# Main.net
KiCad netlist of a schematic drawn in Altium Designer
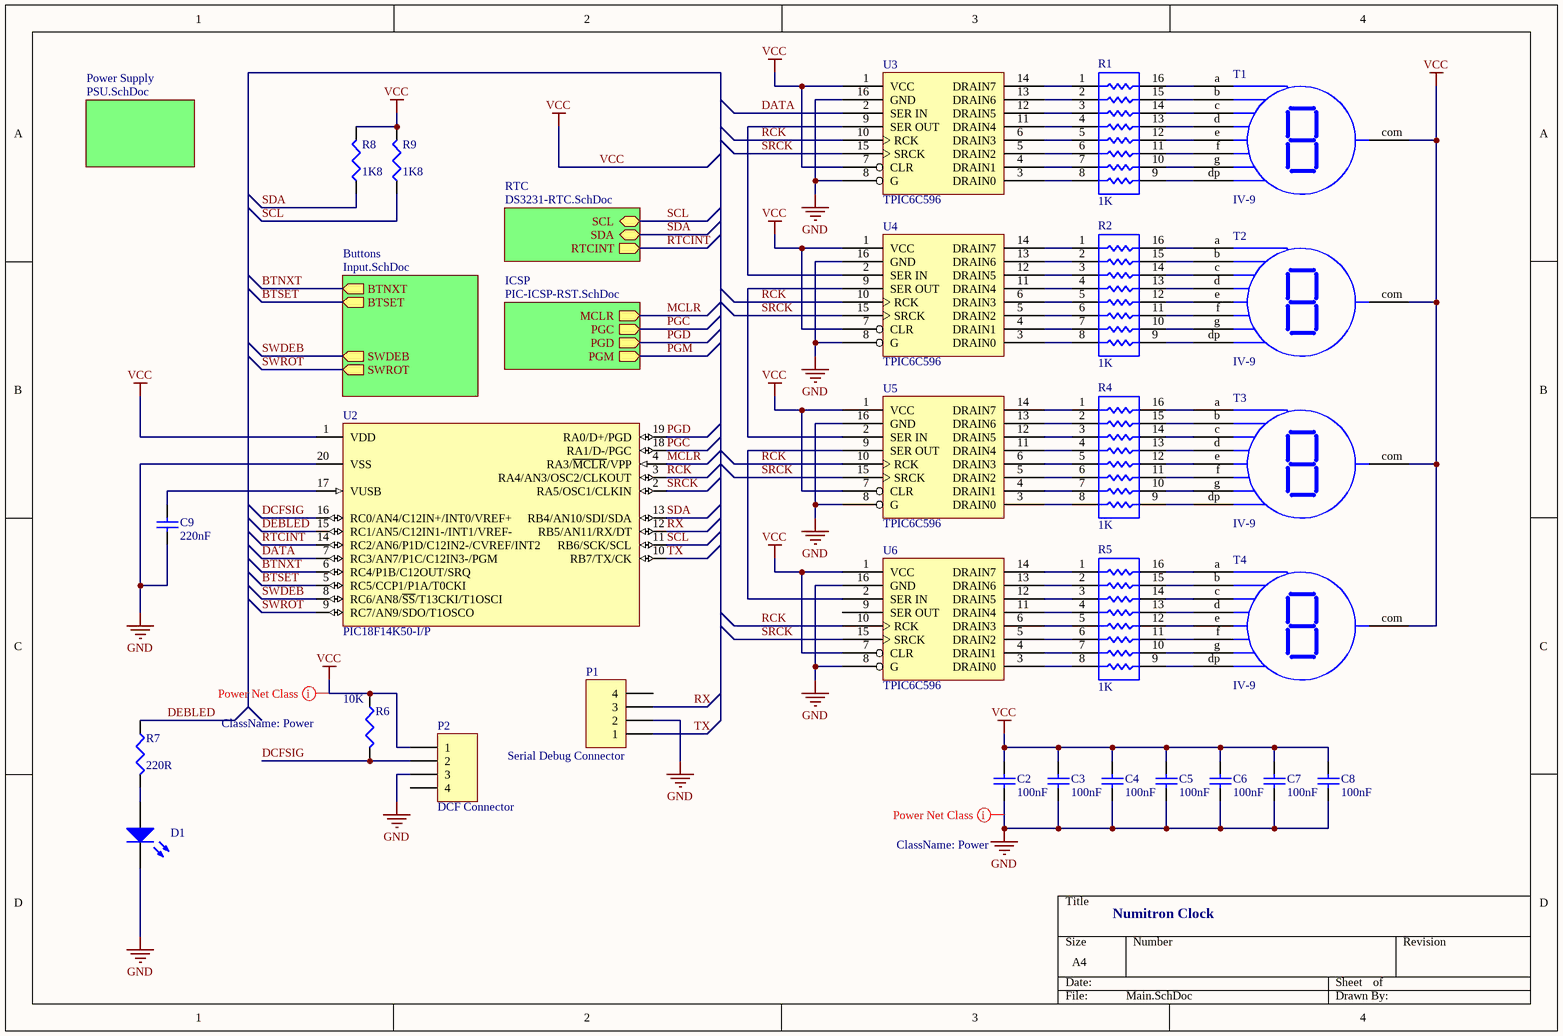
[diagram p0: Main.SchDoc]

(export (version "E")
  (design (tool "Eeschema 10.0.6"))
  (components
    (comp (ref "C2")
      (value "100nF")
      (footprint "RCL 0805")
      (description "Capacitor (Semiconductor SIM Model)")
      (fields (field (name "Comment") "Cap Semi") (field (name "PUBLISHER") "Altium Limited"))
      (libsource (lib "Miscellaneous Devices") (part "Cap Semi"))
    )
    (comp (ref "C3")
      (value "100nF")
      (footprint "RCL 0805")
      (description "Capacitor (Semiconductor SIM Model)")
      (fields (field (name "Comment") "Cap Semi") (field (name "PUBLISHER") "Altium Limited"))
      (libsource (lib "Miscellaneous Devices") (part "Cap Semi"))
    )
    (comp (ref "C4")
      (value "100nF")
      (footprint "RCL 0805")
      (description "Capacitor (Semiconductor SIM Model)")
      (fields (field (name "Comment") "Cap Semi") (field (name "PUBLISHER") "Altium Limited"))
      (libsource (lib "Miscellaneous Devices") (part "Cap Semi"))
    )
    (comp (ref "C5")
      (value "100nF")
      (footprint "RCL 0805")
      (description "Capacitor (Semiconductor SIM Model)")
      (fields (field (name "Comment") "Cap Semi") (field (name "PUBLISHER") "Altium Limited"))
      (libsource (lib "Miscellaneous Devices") (part "Cap Semi"))
    )
    (comp (ref "C6")
      (value "100nF")
      (footprint "RCL 0805")
      (description "Capacitor (Semiconductor SIM Model)")
      (fields (field (name "Comment") "Cap Semi") (field (name "PUBLISHER") "Altium Limited"))
      (libsource (lib "Miscellaneous Devices") (part "Cap Semi"))
    )
    (comp (ref "C7")
      (value "100nF")
      (footprint "RCL 0805")
      (description "Capacitor (Semiconductor SIM Model)")
      (fields (field (name "Comment") "Cap Semi") (field (name "PUBLISHER") "Altium Limited"))
      (libsource (lib "Miscellaneous Devices") (part "Cap Semi"))
    )
    (comp (ref "C8")
      (value "100nF")
      (footprint "RCL 0805")
      (description "Capacitor (Semiconductor SIM Model)")
      (fields (field (name "Comment") "Cap Semi") (field (name "PUBLISHER") "Altium Limited"))
      (libsource (lib "Miscellaneous Devices") (part "Cap Semi"))
    )
    (comp (ref "C9")
      (value "220nF")
      (footprint "RCL 0805")
      (description "Capacitor (Semiconductor SIM Model)")
      (fields (field (name "Comment") "Cap Semi") (field (name "PUBLISHER") "Altium Limited"))
      (libsource (lib "Miscellaneous Devices") (part "Cap Semi"))
    )
    (comp (ref "D1")
      (value "LED2")
      (footprint "RCL 0805 POL")
      (description "Typical RED, GREEN, YELLOW, AMBER GaAs LED")
      (fields (field (name "PUBLISHER") "Altium Limited"))
      (libsource (lib "Miscellaneous Devices") (part "LED2"))
    )
    (comp (ref "P1")
      (value "Serial Debug Connector")
      (footprint "PC Audio Connector")
      (description "Header, 4-Pin")
      (fields (field (name "PUBLISHER") "Altium Limited"))
      (libsource (lib "Miscellaneous Connectors") (part "Header 4"))
    )
    (comp (ref "P2")
      (value "DCF Connector")
      (footprint "PC Audio Connector")
      (description "Header, 4-Pin")
      (fields (field (name "PUBLISHER") "Altium Limited"))
      (libsource (lib "") (part "Header 4_1"))
    )
    (comp (ref "R1")
      (value "1K")
      (footprint "DIP16")
      (description "Isolated Resistor Network")
      (fields (field (name "Comment") "Res Pack3") (field (name "PUBLISHER") "Altium Limited"))
      (libsource (lib "Miscellaneous Devices") (part "Res Pack3"))
    )
    (comp (ref "R2")
      (value "1K")
      (footprint "DIP16")
      (description "Isolated Resistor Network")
      (fields (field (name "Comment") "Res Pack3") (field (name "PUBLISHER") "Altium Limited"))
      (libsource (lib "Miscellaneous Devices") (part "Res Pack3"))
    )
    (comp (ref "R4")
      (value "1K")
      (footprint "DIP16")
      (description "Isolated Resistor Network")
      (fields (field (name "Comment") "Res Pack3") (field (name "PUBLISHER") "Altium Limited"))
      (libsource (lib "Miscellaneous Devices") (part "Res Pack3"))
    )
    (comp (ref "R5")
      (value "1K")
      (footprint "DIP16")
      (description "Isolated Resistor Network")
      (fields (field (name "Comment") "Res Pack3") (field (name "PUBLISHER") "Altium Limited"))
      (libsource (lib "Miscellaneous Devices") (part "Res Pack3"))
    )
    (comp (ref "R6")
      (value "10K")
      (footprint "RCL 0805")
      (description "Resistor")
      (fields (field (name "Comment") "Res3") (field (name "PUBLISHER") "Altium Limited"))
      (libsource (lib "Miscellaneous Devices") (part "Res3"))
    )
    (comp (ref "R7")
      (value "220R")
      (footprint "RCL 0805")
      (description "Resistor")
      (fields (field (name "Comment") "Res3") (field (name "PUBLISHER") "Altium Limited"))
      (libsource (lib "Miscellaneous Devices") (part "Res3"))
    )
    (comp (ref "R8")
      (value "1K8")
      (footprint "RCL 0805")
      (description "Resistor")
      (fields (field (name "Comment") "I2C SDA PULLUP") (field (name "PUBLISHER") "Altium Limited"))
      (libsource (lib "Miscellaneous Devices") (part "Res3"))
    )
    (comp (ref "R9")
      (value "1K8")
      (footprint "RCL 0805")
      (description "Resistor")
      (fields (field (name "Comment") "I2C SCL PULLUP") (field (name "PUBLISHER") "Altium Limited"))
      (libsource (lib "Miscellaneous Devices") (part "Res3"))
    )
    (comp (ref "T1") (value "IV-9") (footprint "IV-9") (libsource (lib "MyLibrary") (part "IV-9")))
    (comp (ref "T2") (value "IV-9") (footprint "IV-9") (libsource (lib "MyLibrary") (part "IV-9")))
    (comp (ref "T3") (value "IV-9") (footprint "IV-9") (libsource (lib "MyLibrary") (part "IV-9")))
    (comp (ref "T4") (value "IV-9") (footprint "IV-9") (libsource (lib "MyLibrary") (part "IV-9")))
    (comp (ref "U2")
      (value "PIC18F14K50-I/P")
      (footprint "DIP20")
      (description "USB Flash Microcontroller with nanoWatt XLP Technology, 20-pin PDIP, Industrial Temperature")
      (fields (field (name "PUBLISHER") "Altium Limited"))
      (libsource (lib "Microchip Microcontroller 8-Bit PIC18") (part "PIC18F14K50-I/P"))
    )
    (comp (ref "U3") (value "TPIC6C596") (footprint "DIP16") (libsource (lib "MyLibrary") (part "TPIC6C596")))
    (comp (ref "U4") (value "TPIC6C596") (footprint "DIP16") (libsource (lib "MyLibrary") (part "TPIC6C596")))
    (comp (ref "U5") (value "TPIC6C596") (footprint "DIP16") (libsource (lib "MyLibrary") (part "TPIC6C596")))
    (comp (ref "U6") (value "TPIC6C596") (footprint "DIP16") (libsource (lib "MyLibrary") (part "TPIC6C596")))
  )
  (nets
    (net (code "1") (name "/BTNXT") (class "Default")
      (node (ref "U2") (pin "6") (pinfunction "RC4/P1B/C12OUT/SRQ_6") (pintype "bidirectional"))
    )
    (net (code "2") (name "/BTSET") (class "Default")
      (node (ref "U2") (pin "5") (pinfunction "RC5/CCP1/P1A/T0CKI_5") (pintype "bidirectional"))
    )
    (net (code "3") (name "/DATA") (class "Default")
      (node (ref "U2") (pin "7") (pinfunction "RC3/AN7/P1C/C12IN3-/PGM_7") (pintype "bidirectional"))
      (node (ref "U3") (pin "2") (pinfunction "SER_IN_2") (pintype "passive"))
    )
    (net (code "4") (name "/DCFSIG") (class "Default")
      (node (ref "P2") (pin "2") (pinfunction "2_2") (pintype "passive"))
      (node (ref "R6") (pin "2") (pinfunction "2_2") (pintype "passive"))
      (node (ref "U2") (pin "16") (pinfunction "RC0/AN4/C12IN+/INT0/VREF+_16") (pintype "bidirectional"))
    )
    (net (code "5") (name "/DEBLED") (class "Default")
      (node (ref "R7") (pin "1") (pinfunction "1_1") (pintype "passive"))
      (node (ref "U2") (pin "15") (pinfunction "RC1/AN5/C12IN1-/INT1/VREF-_15") (pintype "bidirectional"))
    )
    (net (code "6") (name "/MCLR") (class "Default")
      (node (ref "U2") (pin "4") (pinfunction "RA3/~{MCLR}/VPP_4") (pintype "input"))
    )
    (net (code "7") (name "/PGC") (class "Default")
      (node (ref "U2") (pin "18") (pinfunction "RA1/D-/PGC_18") (pintype "bidirectional"))
    )
    (net (code "8") (name "/PGD") (class "Default")
      (node (ref "U2") (pin "19") (pinfunction "RA0/D+/PGD_19") (pintype "bidirectional"))
    )
    (net (code "10") (name "/RCK") (class "Default")
      (node (ref "U2") (pin "3") (pinfunction "RA4/AN3/OSC2/CLKOUT_3") (pintype "bidirectional"))
      (node (ref "U3") (pin "10") (pinfunction "RCK_10") (pintype "passive"))
      (node (ref "U4") (pin "10") (pinfunction "RCK_10") (pintype "passive"))
      (node (ref "U5") (pin "10") (pinfunction "RCK_10") (pintype "passive"))
      (node (ref "U6") (pin "10") (pinfunction "RCK_10") (pintype "passive"))
    )
    (net (code "11") (name "/RTCINT") (class "Default")
      (node (ref "U2") (pin "14") (pinfunction "RC2/AN6/P1D/C12IN2-/CVREF/INT2_14") (pintype "bidirectional"))
    )
    (net (code "12") (name "/RX") (class "Default")
      (node (ref "P1") (pin "3") (pinfunction "3_3") (pintype "passive"))
      (node (ref "U2") (pin "12") (pinfunction "RB5/AN11/RX/DT_12") (pintype "bidirectional"))
    )
    (net (code "13") (name "/SCL") (class "Default")
      (node (ref "R9") (pin "1") (pinfunction "1_1") (pintype "passive"))
      (node (ref "U2") (pin "11") (pinfunction "RB6/SCK/SCL_11") (pintype "bidirectional"))
    )
    (net (code "14") (name "/SDA") (class "Default")
      (node (ref "R8") (pin "1") (pinfunction "1_1") (pintype "passive"))
      (node (ref "U2") (pin "13") (pinfunction "RB4/AN10/SDI/SDA_13") (pintype "bidirectional"))
    )
    (net (code "15") (name "/SRCK") (class "Default")
      (node (ref "U2") (pin "2") (pinfunction "RA5/OSC1/CLKIN_2") (pintype "bidirectional"))
      (node (ref "U3") (pin "15") (pinfunction "SRCK_15") (pintype "passive"))
      (node (ref "U4") (pin "15") (pinfunction "SRCK_15") (pintype "passive"))
      (node (ref "U5") (pin "15") (pinfunction "SRCK_15") (pintype "passive"))
      (node (ref "U6") (pin "15") (pinfunction "SRCK_15") (pintype "passive"))
    )
    (net (code "16") (name "/SWDEB") (class "Default")
      (node (ref "U2") (pin "8") (pinfunction "RC6/AN8/~{SS}/T13CKI/T1OSCI_8") (pintype "bidirectional"))
    )
    (net (code "17") (name "/SWROT") (class "Default")
      (node (ref "U2") (pin "9") (pinfunction "RC7/AN9/SDO/T1OSCO_9") (pintype "bidirectional"))
    )
    (net (code "18") (name "/TX") (class "Default")
      (node (ref "P1") (pin "1") (pinfunction "1_1") (pintype "passive"))
      (node (ref "U2") (pin "10") (pinfunction "RB7/TX/CK_10") (pintype "bidirectional"))
    )
    (net (code "19") (name "GND") (class "Default")
      (node (ref "C2") (pin "1") (pinfunction "1_1") (pintype "passive"))
      (node (ref "C3") (pin "1") (pinfunction "1_1") (pintype "passive"))
      (node (ref "C4") (pin "1") (pinfunction "1_1") (pintype "passive"))
      (node (ref "C5") (pin "1") (pinfunction "1_1") (pintype "passive"))
      (node (ref "C6") (pin "1") (pinfunction "1_1") (pintype "passive"))
      (node (ref "C7") (pin "1") (pinfunction "1_1") (pintype "passive"))
      (node (ref "C8") (pin "1") (pinfunction "1_1") (pintype "passive"))
      (node (ref "C9") (pin "1") (pinfunction "1_1") (pintype "passive"))
      (node (ref "D1") (pin "2") (pinfunction "K_2") (pintype "passive"))
      (node (ref "P1") (pin "2") (pinfunction "2_2") (pintype "passive"))
      (node (ref "P2") (pin "3") (pinfunction "3_3") (pintype "passive"))
      (node (ref "U2") (pin "20") (pinfunction "VSS_20") (pintype "power_in"))
      (node (ref "U3") (pin "16") (pinfunction "GND_16") (pintype "passive"))
      (node (ref "U3") (pin "8") (pinfunction "G_8") (pintype "passive"))
      (node (ref "U4") (pin "16") (pinfunction "GND_16") (pintype "passive"))
      (node (ref "U4") (pin "8") (pinfunction "G_8") (pintype "passive"))
      (node (ref "U5") (pin "16") (pinfunction "GND_16") (pintype "passive"))
      (node (ref "U5") (pin "8") (pinfunction "G_8") (pintype "passive"))
      (node (ref "U6") (pin "16") (pinfunction "GND_16") (pintype "passive"))
      (node (ref "U6") (pin "8") (pinfunction "G_8") (pintype "passive"))
    )
    (net (code "20") (name "Net-(D1-A)") (class "Default")
      (node (ref "D1") (pin "1") (pinfunction "A_1") (pintype "passive"))
      (node (ref "R7") (pin "2") (pinfunction "2_2") (pintype "passive"))
    )
    (net (code "21") (name "Net-(R1-Pad9)") (class "Default")
      (node (ref "R1") (pin "9") (pinfunction "9_9") (pintype "passive"))
      (node (ref "T1") (pin "dp") (pinfunction "dp_dp") (pintype "passive"))
    )
    (net (code "22") (name "Net-(R1-Pad10)") (class "Default")
      (node (ref "R1") (pin "10") (pinfunction "10_10") (pintype "passive"))
      (node (ref "T1") (pin "g") (pinfunction "g_g") (pintype "passive"))
    )
    (net (code "23") (name "Net-(R1-Pad11)") (class "Default")
      (node (ref "R1") (pin "11") (pinfunction "11_11") (pintype "passive"))
      (node (ref "T1") (pin "f") (pinfunction "f_f") (pintype "passive"))
    )
    (net (code "24") (name "Net-(R1-Pad12)") (class "Default")
      (node (ref "R1") (pin "12") (pinfunction "12_12") (pintype "passive"))
      (node (ref "T1") (pin "e") (pinfunction "e_e") (pintype "passive"))
    )
    (net (code "25") (name "Net-(R1-Pad13)") (class "Default")
      (node (ref "R1") (pin "13") (pinfunction "13_13") (pintype "passive"))
      (node (ref "T1") (pin "d") (pinfunction "d_d") (pintype "passive"))
    )
    (net (code "26") (name "Net-(R1-Pad14)") (class "Default")
      (node (ref "R1") (pin "14") (pinfunction "14_14") (pintype "passive"))
      (node (ref "T1") (pin "c") (pinfunction "c_c") (pintype "passive"))
    )
    (net (code "27") (name "Net-(R1-Pad15)") (class "Default")
      (node (ref "R1") (pin "15") (pinfunction "15_15") (pintype "passive"))
      (node (ref "T1") (pin "b") (pinfunction "b_b") (pintype "passive"))
    )
    (net (code "28") (name "Net-(R1-Pad16)") (class "Default")
      (node (ref "R1") (pin "16") (pinfunction "16_16") (pintype "passive"))
      (node (ref "T1") (pin "a") (pinfunction "a_a") (pintype "passive"))
    )
    (net (code "29") (name "Net-(R2-Pad9)") (class "Default")
      (node (ref "R2") (pin "9") (pinfunction "9_9") (pintype "passive"))
      (node (ref "T2") (pin "dp") (pinfunction "dp_dp") (pintype "passive"))
    )
    (net (code "30") (name "Net-(R2-Pad10)") (class "Default")
      (node (ref "R2") (pin "10") (pinfunction "10_10") (pintype "passive"))
      (node (ref "T2") (pin "g") (pinfunction "g_g") (pintype "passive"))
    )
    (net (code "31") (name "Net-(R2-Pad11)") (class "Default")
      (node (ref "R2") (pin "11") (pinfunction "11_11") (pintype "passive"))
      (node (ref "T2") (pin "f") (pinfunction "f_f") (pintype "passive"))
    )
    (net (code "32") (name "Net-(R2-Pad12)") (class "Default")
      (node (ref "R2") (pin "12") (pinfunction "12_12") (pintype "passive"))
      (node (ref "T2") (pin "e") (pinfunction "e_e") (pintype "passive"))
    )
    (net (code "33") (name "Net-(R2-Pad13)") (class "Default")
      (node (ref "R2") (pin "13") (pinfunction "13_13") (pintype "passive"))
      (node (ref "T2") (pin "d") (pinfunction "d_d") (pintype "passive"))
    )
    (net (code "34") (name "Net-(R2-Pad14)") (class "Default")
      (node (ref "R2") (pin "14") (pinfunction "14_14") (pintype "passive"))
      (node (ref "T2") (pin "c") (pinfunction "c_c") (pintype "passive"))
    )
    (net (code "35") (name "Net-(R2-Pad15)") (class "Default")
      (node (ref "R2") (pin "15") (pinfunction "15_15") (pintype "passive"))
      (node (ref "T2") (pin "b") (pinfunction "b_b") (pintype "passive"))
    )
    (net (code "36") (name "Net-(R2-Pad16)") (class "Default")
      (node (ref "R2") (pin "16") (pinfunction "16_16") (pintype "passive"))
      (node (ref "T2") (pin "a") (pinfunction "a_a") (pintype "passive"))
    )
    (net (code "37") (name "Net-(R4-Pad9)") (class "Default")
      (node (ref "R4") (pin "9") (pinfunction "9_9") (pintype "passive"))
      (node (ref "T3") (pin "dp") (pinfunction "dp_dp") (pintype "passive"))
    )
    (net (code "38") (name "Net-(R4-Pad10)") (class "Default")
      (node (ref "R4") (pin "10") (pinfunction "10_10") (pintype "passive"))
      (node (ref "T3") (pin "g") (pinfunction "g_g") (pintype "passive"))
    )
    (net (code "39") (name "Net-(R4-Pad11)") (class "Default")
      (node (ref "R4") (pin "11") (pinfunction "11_11") (pintype "passive"))
      (node (ref "T3") (pin "f") (pinfunction "f_f") (pintype "passive"))
    )
    (net (code "40") (name "Net-(R4-Pad12)") (class "Default")
      (node (ref "R4") (pin "12") (pinfunction "12_12") (pintype "passive"))
      (node (ref "T3") (pin "e") (pinfunction "e_e") (pintype "passive"))
    )
    (net (code "41") (name "Net-(R4-Pad13)") (class "Default")
      (node (ref "R4") (pin "13") (pinfunction "13_13") (pintype "passive"))
      (node (ref "T3") (pin "d") (pinfunction "d_d") (pintype "passive"))
    )
    (net (code "42") (name "Net-(R4-Pad14)") (class "Default")
      (node (ref "R4") (pin "14") (pinfunction "14_14") (pintype "passive"))
      (node (ref "T3") (pin "c") (pinfunction "c_c") (pintype "passive"))
    )
    (net (code "43") (name "Net-(R4-Pad15)") (class "Default")
      (node (ref "R4") (pin "15") (pinfunction "15_15") (pintype "passive"))
      (node (ref "T3") (pin "b") (pinfunction "b_b") (pintype "passive"))
    )
    (net (code "44") (name "Net-(R4-Pad16)") (class "Default")
      (node (ref "R4") (pin "16") (pinfunction "16_16") (pintype "passive"))
      (node (ref "T3") (pin "a") (pinfunction "a_a") (pintype "passive"))
    )
    (net (code "45") (name "Net-(R5-Pad9)") (class "Default")
      (node (ref "R5") (pin "9") (pinfunction "9_9") (pintype "passive"))
      (node (ref "T4") (pin "dp") (pinfunction "dp_dp") (pintype "passive"))
    )
    (net (code "46") (name "Net-(R5-Pad10)") (class "Default")
      (node (ref "R5") (pin "10") (pinfunction "10_10") (pintype "passive"))
      (node (ref "T4") (pin "g") (pinfunction "g_g") (pintype "passive"))
    )
    (net (code "47") (name "Net-(R5-Pad11)") (class "Default")
      (node (ref "R5") (pin "11") (pinfunction "11_11") (pintype "passive"))
      (node (ref "T4") (pin "f") (pinfunction "f_f") (pintype "passive"))
    )
    (net (code "48") (name "Net-(R5-Pad12)") (class "Default")
      (node (ref "R5") (pin "12") (pinfunction "12_12") (pintype "passive"))
      (node (ref "T4") (pin "e") (pinfunction "e_e") (pintype "passive"))
    )
    (net (code "49") (name "Net-(R5-Pad13)") (class "Default")
      (node (ref "R5") (pin "13") (pinfunction "13_13") (pintype "passive"))
      (node (ref "T4") (pin "d") (pinfunction "d_d") (pintype "passive"))
    )
    (net (code "50") (name "Net-(R5-Pad14)") (class "Default")
      (node (ref "R5") (pin "14") (pinfunction "14_14") (pintype "passive"))
      (node (ref "T4") (pin "c") (pinfunction "c_c") (pintype "passive"))
    )
    (net (code "51") (name "Net-(R5-Pad15)") (class "Default")
      (node (ref "R5") (pin "15") (pinfunction "15_15") (pintype "passive"))
      (node (ref "T4") (pin "b") (pinfunction "b_b") (pintype "passive"))
    )
    (net (code "52") (name "Net-(R5-Pad16)") (class "Default")
      (node (ref "R5") (pin "16") (pinfunction "16_16") (pintype "passive"))
      (node (ref "T4") (pin "a") (pinfunction "a_a") (pintype "passive"))
    )
    (net (code "53") (name "Net-(U2-VUSB)") (class "Default")
      (node (ref "C9") (pin "2") (pinfunction "2_2") (pintype "passive"))
      (node (ref "U2") (pin "17") (pinfunction "VUSB_17") (pintype "input"))
    )
    (net (code "54") (name "Net-(U3-DRAIN0)") (class "Default")
      (node (ref "R1") (pin "8") (pinfunction "8_8") (pintype "passive"))
      (node (ref "U3") (pin "3") (pinfunction "DRAIN0_3") (pintype "passive"))
    )
    (net (code "55") (name "Net-(U3-DRAIN1)") (class "Default")
      (node (ref "R1") (pin "7") (pinfunction "7_7") (pintype "passive"))
      (node (ref "U3") (pin "4") (pinfunction "DRAIN1_4") (pintype "passive"))
    )
    (net (code "56") (name "Net-(U3-DRAIN2)") (class "Default")
      (node (ref "R1") (pin "6") (pinfunction "6_6") (pintype "passive"))
      (node (ref "U3") (pin "5") (pinfunction "DRAIN2_5") (pintype "passive"))
    )
    (net (code "57") (name "Net-(U3-DRAIN3)") (class "Default")
      (node (ref "R1") (pin "5") (pinfunction "5_5") (pintype "passive"))
      (node (ref "U3") (pin "6") (pinfunction "DRAIN3_6") (pintype "passive"))
    )
    (net (code "58") (name "Net-(U3-DRAIN4)") (class "Default")
      (node (ref "R1") (pin "4") (pinfunction "4_4") (pintype "passive"))
      (node (ref "U3") (pin "11") (pinfunction "DRAIN4_11") (pintype "passive"))
    )
    (net (code "59") (name "Net-(U3-DRAIN5)") (class "Default")
      (node (ref "R1") (pin "3") (pinfunction "3_3") (pintype "passive"))
      (node (ref "U3") (pin "12") (pinfunction "DRAIN5_12") (pintype "passive"))
    )
    (net (code "60") (name "Net-(U3-DRAIN6)") (class "Default")
      (node (ref "R1") (pin "2") (pinfunction "2_2") (pintype "passive"))
      (node (ref "U3") (pin "13") (pinfunction "DRAIN6_13") (pintype "passive"))
    )
    (net (code "61") (name "Net-(U3-DRAIN7)") (class "Default")
      (node (ref "R1") (pin "1") (pinfunction "1_1") (pintype "passive"))
      (node (ref "U3") (pin "14") (pinfunction "DRAIN7_14") (pintype "passive"))
    )
    (net (code "62") (name "Net-(U3-SER_OUT)") (class "Default")
      (node (ref "U3") (pin "9") (pinfunction "SER_OUT_9") (pintype "passive"))
      (node (ref "U4") (pin "2") (pinfunction "SER_IN_2") (pintype "passive"))
    )
    (net (code "63") (name "Net-(U4-DRAIN0)") (class "Default")
      (node (ref "R2") (pin "8") (pinfunction "8_8") (pintype "passive"))
      (node (ref "U4") (pin "3") (pinfunction "DRAIN0_3") (pintype "passive"))
    )
    (net (code "64") (name "Net-(U4-DRAIN1)") (class "Default")
      (node (ref "R2") (pin "7") (pinfunction "7_7") (pintype "passive"))
      (node (ref "U4") (pin "4") (pinfunction "DRAIN1_4") (pintype "passive"))
    )
    (net (code "65") (name "Net-(U4-DRAIN2)") (class "Default")
      (node (ref "R2") (pin "6") (pinfunction "6_6") (pintype "passive"))
      (node (ref "U4") (pin "5") (pinfunction "DRAIN2_5") (pintype "passive"))
    )
    (net (code "66") (name "Net-(U4-DRAIN3)") (class "Default")
      (node (ref "R2") (pin "5") (pinfunction "5_5") (pintype "passive"))
      (node (ref "U4") (pin "6") (pinfunction "DRAIN3_6") (pintype "passive"))
    )
    (net (code "67") (name "Net-(U4-DRAIN4)") (class "Default")
      (node (ref "R2") (pin "4") (pinfunction "4_4") (pintype "passive"))
      (node (ref "U4") (pin "11") (pinfunction "DRAIN4_11") (pintype "passive"))
    )
    (net (code "68") (name "Net-(U4-DRAIN5)") (class "Default")
      (node (ref "R2") (pin "3") (pinfunction "3_3") (pintype "passive"))
      (node (ref "U4") (pin "12") (pinfunction "DRAIN5_12") (pintype "passive"))
    )
    (net (code "69") (name "Net-(U4-DRAIN6)") (class "Default")
      (node (ref "R2") (pin "2") (pinfunction "2_2") (pintype "passive"))
      (node (ref "U4") (pin "13") (pinfunction "DRAIN6_13") (pintype "passive"))
    )
    (net (code "70") (name "Net-(U4-DRAIN7)") (class "Default")
      (node (ref "R2") (pin "1") (pinfunction "1_1") (pintype "passive"))
      (node (ref "U4") (pin "14") (pinfunction "DRAIN7_14") (pintype "passive"))
    )
    (net (code "71") (name "Net-(U4-SER_OUT)") (class "Default")
      (node (ref "U4") (pin "9") (pinfunction "SER_OUT_9") (pintype "passive"))
      (node (ref "U5") (pin "2") (pinfunction "SER_IN_2") (pintype "passive"))
    )
    (net (code "72") (name "Net-(U5-DRAIN0)") (class "Default")
      (node (ref "R4") (pin "8") (pinfunction "8_8") (pintype "passive"))
      (node (ref "U5") (pin "3") (pinfunction "DRAIN0_3") (pintype "passive"))
    )
    (net (code "73") (name "Net-(U5-DRAIN1)") (class "Default")
      (node (ref "R4") (pin "7") (pinfunction "7_7") (pintype "passive"))
      (node (ref "U5") (pin "4") (pinfunction "DRAIN1_4") (pintype "passive"))
    )
    (net (code "74") (name "Net-(U5-DRAIN2)") (class "Default")
      (node (ref "R4") (pin "6") (pinfunction "6_6") (pintype "passive"))
      (node (ref "U5") (pin "5") (pinfunction "DRAIN2_5") (pintype "passive"))
    )
    (net (code "75") (name "Net-(U5-DRAIN3)") (class "Default")
      (node (ref "R4") (pin "5") (pinfunction "5_5") (pintype "passive"))
      (node (ref "U5") (pin "6") (pinfunction "DRAIN3_6") (pintype "passive"))
    )
    (net (code "76") (name "Net-(U5-DRAIN4)") (class "Default")
      (node (ref "R4") (pin "4") (pinfunction "4_4") (pintype "passive"))
      (node (ref "U5") (pin "11") (pinfunction "DRAIN4_11") (pintype "passive"))
    )
    (net (code "77") (name "Net-(U5-DRAIN5)") (class "Default")
      (node (ref "R4") (pin "3") (pinfunction "3_3") (pintype "passive"))
      (node (ref "U5") (pin "12") (pinfunction "DRAIN5_12") (pintype "passive"))
    )
    (net (code "78") (name "Net-(U5-DRAIN6)") (class "Default")
      (node (ref "R4") (pin "2") (pinfunction "2_2") (pintype "passive"))
      (node (ref "U5") (pin "13") (pinfunction "DRAIN6_13") (pintype "passive"))
    )
    (net (code "79") (name "Net-(U5-DRAIN7)") (class "Default")
      (node (ref "R4") (pin "1") (pinfunction "1_1") (pintype "passive"))
      (node (ref "U5") (pin "14") (pinfunction "DRAIN7_14") (pintype "passive"))
    )
    (net (code "80") (name "Net-(U5-SER_OUT)") (class "Default")
      (node (ref "U5") (pin "9") (pinfunction "SER_OUT_9") (pintype "passive"))
      (node (ref "U6") (pin "2") (pinfunction "SER_IN_2") (pintype "passive"))
    )
    (net (code "81") (name "Net-(U6-DRAIN0)") (class "Default")
      (node (ref "R5") (pin "8") (pinfunction "8_8") (pintype "passive"))
      (node (ref "U6") (pin "3") (pinfunction "DRAIN0_3") (pintype "passive"))
    )
    (net (code "82") (name "Net-(U6-DRAIN1)") (class "Default")
      (node (ref "R5") (pin "7") (pinfunction "7_7") (pintype "passive"))
      (node (ref "U6") (pin "4") (pinfunction "DRAIN1_4") (pintype "passive"))
    )
    (net (code "83") (name "Net-(U6-DRAIN2)") (class "Default")
      (node (ref "R5") (pin "6") (pinfunction "6_6") (pintype "passive"))
      (node (ref "U6") (pin "5") (pinfunction "DRAIN2_5") (pintype "passive"))
    )
    (net (code "84") (name "Net-(U6-DRAIN3)") (class "Default")
      (node (ref "R5") (pin "5") (pinfunction "5_5") (pintype "passive"))
      (node (ref "U6") (pin "6") (pinfunction "DRAIN3_6") (pintype "passive"))
    )
    (net (code "85") (name "Net-(U6-DRAIN4)") (class "Default")
      (node (ref "R5") (pin "4") (pinfunction "4_4") (pintype "passive"))
      (node (ref "U6") (pin "11") (pinfunction "DRAIN4_11") (pintype "passive"))
    )
    (net (code "86") (name "Net-(U6-DRAIN5)") (class "Default")
      (node (ref "R5") (pin "3") (pinfunction "3_3") (pintype "passive"))
      (node (ref "U6") (pin "12") (pinfunction "DRAIN5_12") (pintype "passive"))
    )
    (net (code "87") (name "Net-(U6-DRAIN6)") (class "Default")
      (node (ref "R5") (pin "2") (pinfunction "2_2") (pintype "passive"))
      (node (ref "U6") (pin "13") (pinfunction "DRAIN6_13") (pintype "passive"))
    )
    (net (code "88") (name "Net-(U6-DRAIN7)") (class "Default")
      (node (ref "R5") (pin "1") (pinfunction "1_1") (pintype "passive"))
      (node (ref "U6") (pin "14") (pinfunction "DRAIN7_14") (pintype "passive"))
    )
    (net (code "89") (name "VCC") (class "Default")
      (node (ref "C2") (pin "2") (pinfunction "2_2") (pintype "passive"))
      (node (ref "C3") (pin "2") (pinfunction "2_2") (pintype "passive"))
      (node (ref "C4") (pin "2") (pinfunction "2_2") (pintype "passive"))
      (node (ref "C5") (pin "2") (pinfunction "2_2") (pintype "passive"))
      (node (ref "C6") (pin "2") (pinfunction "2_2") (pintype "passive"))
      (node (ref "C7") (pin "2") (pinfunction "2_2") (pintype "passive"))
      (node (ref "C8") (pin "2") (pinfunction "2_2") (pintype "passive"))
      (node (ref "P2") (pin "1") (pinfunction "1_1") (pintype "passive"))
      (node (ref "R6") (pin "1") (pinfunction "1_1") (pintype "passive"))
      (node (ref "R8") (pin "2") (pinfunction "2_2") (pintype "passive"))
      (node (ref "R9") (pin "2") (pinfunction "2_2") (pintype "passive"))
      (node (ref "T1") (pin "com") (pinfunction "com_com") (pintype "passive"))
      (node (ref "T2") (pin "com") (pinfunction "com_com") (pintype "passive"))
      (node (ref "T3") (pin "com") (pinfunction "com_com") (pintype "passive"))
      (node (ref "T4") (pin "com") (pinfunction "com_com") (pintype "passive"))
      (node (ref "U2") (pin "1") (pinfunction "VDD_1") (pintype "power_in"))
      (node (ref "U3") (pin "1") (pinfunction "VCC_1") (pintype "passive"))
      (node (ref "U3") (pin "7") (pinfunction "CLR_7") (pintype "passive"))
      (node (ref "U4") (pin "1") (pinfunction "VCC_1") (pintype "passive"))
      (node (ref "U4") (pin "7") (pinfunction "CLR_7") (pintype "passive"))
      (node (ref "U5") (pin "1") (pinfunction "VCC_1") (pintype "passive"))
      (node (ref "U5") (pin "7") (pinfunction "CLR_7") (pintype "passive"))
      (node (ref "U6") (pin "1") (pinfunction "VCC_1") (pintype "passive"))
      (node (ref "U6") (pin "7") (pinfunction "CLR_7") (pintype "passive"))
    )
    (net (code "90") (name "unconnected-(P1-Pad4)") (class "Default")
      (node (ref "P1") (pin "4") (pinfunction "4_4") (pintype "passive"))
    )
    (net (code "91") (name "unconnected-(P2-Pad4)") (class "Default")
      (node (ref "P2") (pin "4") (pinfunction "4_4") (pintype "passive"))
    )
    (net (code "92") (name "unconnected-(U6-SER_OUT-Pad9)") (class "Default")
      (node (ref "U6") (pin "9") (pinfunction "SER_OUT_9") (pintype "passive"))
    )
  )
)
